# radiomatrix.net
KiCad netlist of a schematic drawn in EAGLE
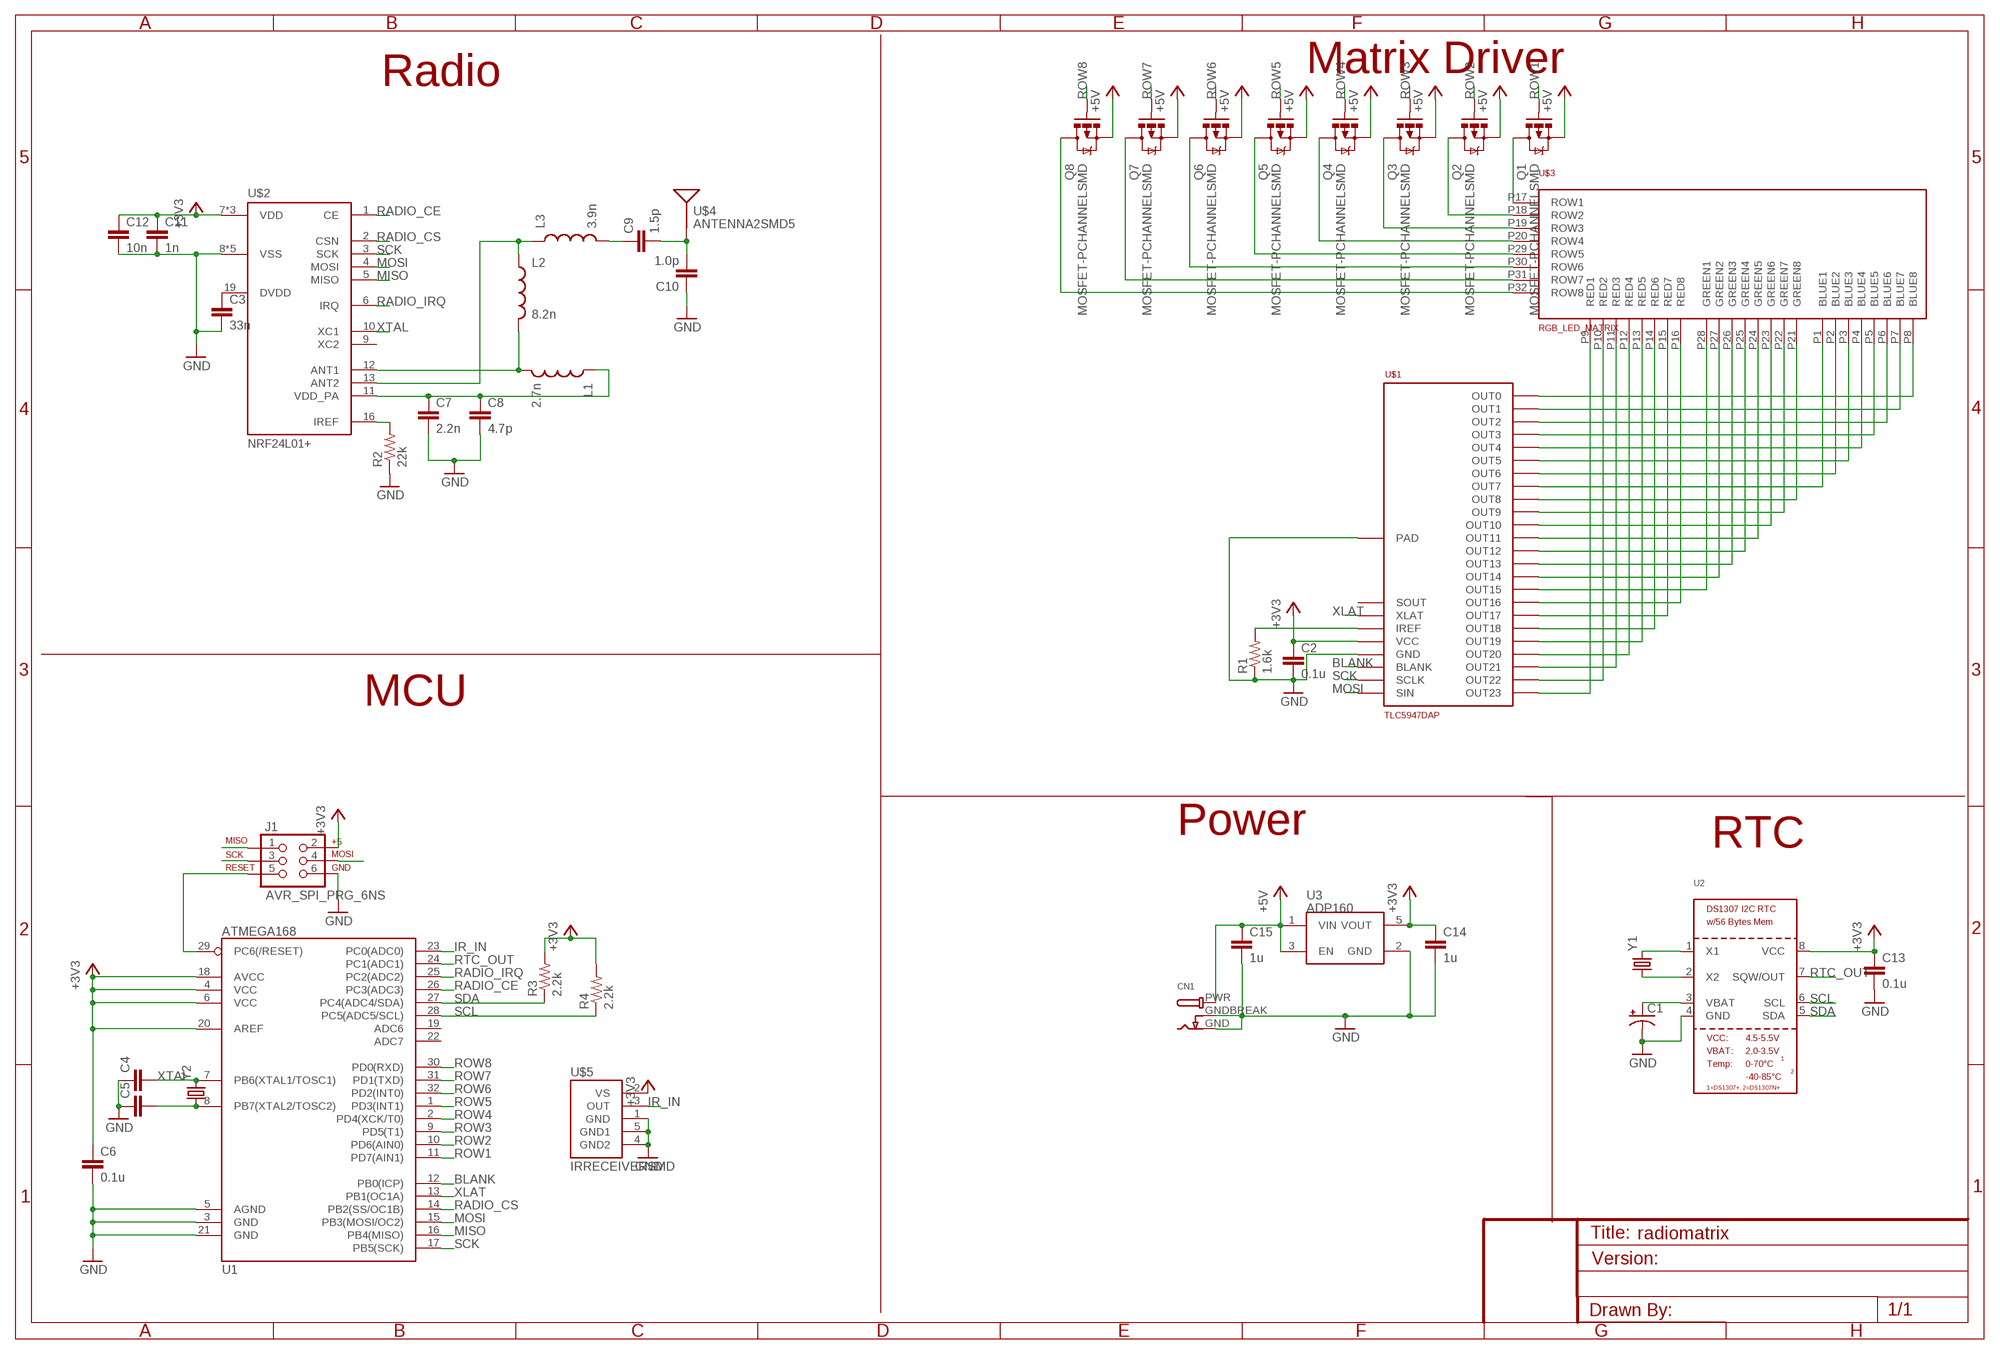
[diagram p0: schematic, sheet 1]

(export (version "E")
  (design (tool "Eeschema 10.0.6"))
  (components
    (comp (ref "C1")
      (value "SUPERCAP")
      (footprint "eagle-import:414-VA5R")
      (libsource (lib "eagle-import") (part "SUPERCAP"))
    )
    (comp (ref "C2")
      (value "0.1u")
      (footprint "eagle-import:0603-CAP")
      (libsource (lib "eagle-import") (part "CAP0603-CAP"))
    )
    (comp (ref "C3")
      (value "33n")
      (footprint "eagle-import:0603-CAP")
      (libsource (lib "eagle-import") (part "CAP0603-CAP"))
    )
    (comp (ref "C4")
      (value "CAP0603-CAP")
      (footprint "eagle-import:0603-CAP")
      (libsource (lib "eagle-import") (part "CAP0603-CAP"))
    )
    (comp (ref "C5")
      (value "CAP0603-CAP")
      (footprint "eagle-import:0603-CAP")
      (libsource (lib "eagle-import") (part "CAP0603-CAP"))
    )
    (comp (ref "C6")
      (value "0.1u")
      (footprint "eagle-import:0603-CAP")
      (libsource (lib "eagle-import") (part "CAP0603-CAP"))
    )
    (comp (ref "C7")
      (value "2.2n")
      (footprint "eagle-import:0603-CAP")
      (libsource (lib "eagle-import") (part "CAP0603-CAP"))
    )
    (comp (ref "C8")
      (value "4.7p")
      (footprint "eagle-import:0603-CAP")
      (libsource (lib "eagle-import") (part "CAP0603-CAP"))
    )
    (comp (ref "C9")
      (value "1.5p")
      (footprint "eagle-import:0603-CAP")
      (libsource (lib "eagle-import") (part "CAP0603-CAP"))
    )
    (comp (ref "C10")
      (value "1.0p")
      (footprint "eagle-import:0603-CAP")
      (libsource (lib "eagle-import") (part "CAP0603-CAP"))
    )
    (comp (ref "C11")
      (value "1n")
      (footprint "eagle-import:0603-CAP")
      (libsource (lib "eagle-import") (part "CAP0603-CAP"))
    )
    (comp (ref "C12")
      (value "10n")
      (footprint "eagle-import:0603-CAP")
      (libsource (lib "eagle-import") (part "CAP0603-CAP"))
    )
    (comp (ref "C13")
      (value "0.1u")
      (footprint "eagle-import:0603-CAP")
      (libsource (lib "eagle-import") (part "CAP0603-CAP"))
    )
    (comp (ref "C14")
      (value "1u")
      (footprint "eagle-import:0603-CAP")
      (libsource (lib "eagle-import") (part "CAP0603-CAP"))
    )
    (comp (ref "C15")
      (value "1u")
      (footprint "eagle-import:0603-CAP")
      (libsource (lib "eagle-import") (part "CAP0603-CAP"))
    )
    (comp (ref "CN1")
      (value "DCBARREL1.3MM")
      (footprint "eagle-import:DCJACK_1.3MM_PTH")
      (libsource (lib "eagle-import") (part "DCBARREL1.3MM"))
    )
    (comp (ref "J1")
      (value "AVR_SPI_PRG_6NS")
      (footprint "eagle-import:2X3-NS")
      (libsource (lib "eagle-import") (part "AVR_SPI_PRG_6NS"))
    )
    (comp (ref "L1")
      (value "2.7n")
      (footprint "eagle-import:0603")
      (libsource (lib "eagle-import") (part "INDUCTOR0603"))
    )
    (comp (ref "L2")
      (value "8.2n")
      (footprint "eagle-import:0603")
      (libsource (lib "eagle-import") (part "INDUCTOR0603"))
    )
    (comp (ref "L3")
      (value "3.9n")
      (footprint "eagle-import:0603")
      (libsource (lib "eagle-import") (part "INDUCTOR0603"))
    )
    (comp (ref "Q1")
      (value "MOSFET-PCHANNELSMD")
      (footprint "eagle-import:SOT23-3")
      (libsource (lib "eagle-import") (part "MOSFET-PCHANNELSMD"))
    )
    (comp (ref "Q2")
      (value "MOSFET-PCHANNELSMD")
      (footprint "eagle-import:SOT23-3")
      (libsource (lib "eagle-import") (part "MOSFET-PCHANNELSMD"))
    )
    (comp (ref "Q3")
      (value "MOSFET-PCHANNELSMD")
      (footprint "eagle-import:SOT23-3")
      (libsource (lib "eagle-import") (part "MOSFET-PCHANNELSMD"))
    )
    (comp (ref "Q4")
      (value "MOSFET-PCHANNELSMD")
      (footprint "eagle-import:SOT23-3")
      (libsource (lib "eagle-import") (part "MOSFET-PCHANNELSMD"))
    )
    (comp (ref "Q5")
      (value "MOSFET-PCHANNELSMD")
      (footprint "eagle-import:SOT23-3")
      (libsource (lib "eagle-import") (part "MOSFET-PCHANNELSMD"))
    )
    (comp (ref "Q6")
      (value "MOSFET-PCHANNELSMD")
      (footprint "eagle-import:SOT23-3")
      (libsource (lib "eagle-import") (part "MOSFET-PCHANNELSMD"))
    )
    (comp (ref "Q7")
      (value "MOSFET-PCHANNELSMD")
      (footprint "eagle-import:SOT23-3")
      (libsource (lib "eagle-import") (part "MOSFET-PCHANNELSMD"))
    )
    (comp (ref "Q8")
      (value "MOSFET-PCHANNELSMD")
      (footprint "eagle-import:SOT23-3")
      (libsource (lib "eagle-import") (part "MOSFET-PCHANNELSMD"))
    )
    (comp (ref "R1")
      (value "1.6k")
      (footprint "eagle-import:0603-RES")
      (libsource (lib "eagle-import") (part "RESISTOR0603-RES"))
    )
    (comp (ref "R2")
      (value "22k")
      (footprint "eagle-import:0603-RES")
      (libsource (lib "eagle-import") (part "RESISTOR0603-RES"))
    )
    (comp (ref "R3")
      (value "2.2k")
      (footprint "eagle-import:0603-RES")
      (libsource (lib "eagle-import") (part "RESISTOR0603-RES"))
    )
    (comp (ref "R4")
      (value "2.2k")
      (footprint "eagle-import:0603-RES")
      (libsource (lib "eagle-import") (part "RESISTOR0603-RES"))
    )
    (comp (ref "U$1")
      (value "TLC5947DAP")
      (footprint "eagle-import:HTSSOP32DAP")
      (libsource (lib "eagle-import") (part "TLC5947DAP"))
    )
    (comp (ref "U$2")
      (value "NRF24L01+")
      (footprint "eagle-import:QFN20")
      (libsource (lib "eagle-import") (part "NRF24L01+"))
    )
    (comp (ref "U$3")
      (value "RGB_LED_MATRIX")
      (footprint "eagle-import:RGB_LED_MATRIX_60MM")
      (libsource (lib "eagle-import") (part "RGB_LED_MATRIX"))
    )
    (comp (ref "U$4")
      (value "ANTENNA2SMD5")
      (footprint "eagle-import:ANTENNA-CHIP5")
      (libsource (lib "eagle-import") (part "ANTENNA2SMD5"))
    )
    (comp (ref "U$5")
      (value "IRRECEIVERSMD")
      (footprint "eagle-import:TSOP8523")
      (libsource (lib "eagle-import") (part "IRRECEIVERSMD"))
    )
    (comp (ref "U1")
      (value "ATMEGA168")
      (footprint "eagle-import:TQFP32-08")
      (libsource (lib "eagle-import") (part "ATMEGA168"))
    )
    (comp (ref "U2")
      (value "RTC_DS1307")
      (footprint "eagle-import:SOIC8_150MIL")
      (libsource (lib "eagle-import") (part "RTC_DS1307"))
    )
    (comp (ref "U3")
      (value "ADP160")
      (footprint "eagle-import:SOT23-5")
      (libsource (lib "eagle-import") (part "ADP160"))
    )
    (comp (ref "Y1")
      (value "CRYSTAL32-SMD")
      (footprint "eagle-import:CRYSTAL-32KHZ-SMD")
      (libsource (lib "eagle-import") (part "CRYSTAL32-SMD"))
    )
    (comp (ref "Y2")
      (value "CRYSTAL5X3")
      (footprint "eagle-import:CRYSTAL-SMD-5X3")
      (libsource (lib "eagle-import") (part "CRYSTAL5X3"))
    )
  )
  (nets
    (net (code "1") (name "+3V3") (class "Default")
      (node (ref "C11") (pin "1") (pinfunction "1_1") (pintype "passive"))
      (node (ref "C12") (pin "1") (pinfunction "1_1") (pintype "passive"))
      (node (ref "C13") (pin "1") (pinfunction "1_1") (pintype "passive"))
      (node (ref "C14") (pin "1") (pinfunction "1_1") (pintype "passive"))
      (node (ref "C2") (pin "1") (pinfunction "1_1") (pintype "passive"))
      (node (ref "C6") (pin "1") (pinfunction "1_1") (pintype "passive"))
      (node (ref "J1") (pin "2") (pinfunction "2_2") (pintype "passive"))
      (node (ref "R3") (pin "2") (pinfunction "2_2") (pintype "passive"))
      (node (ref "R4") (pin "2") (pinfunction "2_2") (pintype "passive"))
      (node (ref "U$1") (pin "32") (pinfunction "VCC_32") (pintype "bidirectional"))
      (node (ref "U$2") (pin "15") (pinfunction "VDD_15") (pintype "bidirectional"))
      (node (ref "U$2") (pin "18") (pinfunction "VDD_18") (pintype "bidirectional"))
      (node (ref "U$2") (pin "7") (pinfunction "VDD_7") (pintype "bidirectional"))
      (node (ref "U$5") (pin "2") (pinfunction "VS_2") (pintype "bidirectional"))
      (node (ref "U1") (pin "18") (pinfunction "AVCC_18") (pintype "bidirectional"))
      (node (ref "U1") (pin "20") (pinfunction "AREF_20") (pintype "bidirectional"))
      (node (ref "U1") (pin "4") (pinfunction "VCC_4") (pintype "bidirectional"))
      (node (ref "U1") (pin "6") (pinfunction "VCC_6") (pintype "bidirectional"))
      (node (ref "U2") (pin "8") (pinfunction "VCC_8") (pintype "bidirectional"))
      (node (ref "U3") (pin "5") (pinfunction "VOUT_5") (pintype "bidirectional"))
    )
    (net (code "2") (name "+5V") (class "Default")
      (node (ref "C15") (pin "1") (pinfunction "1_1") (pintype "passive"))
      (node (ref "CN1") (pin "PWR") (pinfunction "PWR_PWR") (pintype "power_in"))
      (node (ref "Q1") (pin "2") (pinfunction "S_2") (pintype "passive"))
      (node (ref "Q2") (pin "2") (pinfunction "S_2") (pintype "passive"))
      (node (ref "Q3") (pin "2") (pinfunction "S_2") (pintype "passive"))
      (node (ref "Q4") (pin "2") (pinfunction "S_2") (pintype "passive"))
      (node (ref "Q5") (pin "2") (pinfunction "S_2") (pintype "passive"))
      (node (ref "Q6") (pin "2") (pinfunction "S_2") (pintype "passive"))
      (node (ref "Q7") (pin "2") (pinfunction "S_2") (pintype "passive"))
      (node (ref "Q8") (pin "2") (pinfunction "S_2") (pintype "passive"))
      (node (ref "U3") (pin "1") (pinfunction "VIN_1") (pintype "bidirectional"))
      (node (ref "U3") (pin "3") (pinfunction "EN_3") (pintype "bidirectional"))
    )
    (net (code "3") (name "/BLANK") (class "Default")
      (node (ref "U$1") (pin "2") (pinfunction "BLANK_2") (pintype "bidirectional"))
      (node (ref "U1") (pin "12") (pinfunction "PB0(ICP)_12") (pintype "bidirectional"))
    )
    (net (code "4") (name "/IR_IN") (class "Default")
      (node (ref "U$5") (pin "3") (pinfunction "OUT_3") (pintype "bidirectional"))
      (node (ref "U1") (pin "23") (pinfunction "PC0(ADC0)_23") (pintype "bidirectional"))
    )
    (net (code "5") (name "/MISO") (class "Default")
      (node (ref "J1") (pin "1") (pinfunction "1_1") (pintype "passive"))
      (node (ref "U$2") (pin "5") (pinfunction "MISO_5") (pintype "bidirectional"))
      (node (ref "U1") (pin "16") (pinfunction "PB4(MISO)_16") (pintype "bidirectional"))
    )
    (net (code "6") (name "/MOSI") (class "Default")
      (node (ref "J1") (pin "4") (pinfunction "4_4") (pintype "passive"))
      (node (ref "U$1") (pin "4") (pinfunction "SIN_4") (pintype "bidirectional"))
      (node (ref "U$2") (pin "4") (pinfunction "MOSI_4") (pintype "bidirectional"))
      (node (ref "U1") (pin "15") (pinfunction "PB3(MOSI/OC2)_15") (pintype "bidirectional"))
    )
    (net (code "7") (name "/RADIO_CE") (class "Default")
      (node (ref "U$2") (pin "1") (pinfunction "CE_1") (pintype "bidirectional"))
      (node (ref "U1") (pin "26") (pinfunction "PC3(ADC3)_26") (pintype "bidirectional"))
    )
    (net (code "8") (name "/RADIO_CS") (class "Default")
      (node (ref "U$2") (pin "2") (pinfunction "CSN_2") (pintype "bidirectional"))
      (node (ref "U1") (pin "14") (pinfunction "PB2(SS/OC1B)_14") (pintype "bidirectional"))
    )
    (net (code "9") (name "/RADIO_IRQ") (class "Default")
      (node (ref "U$2") (pin "6") (pinfunction "IRQ_6") (pintype "bidirectional"))
      (node (ref "U1") (pin "25") (pinfunction "PC2(ADC2)_25") (pintype "bidirectional"))
    )
    (net (code "10") (name "/ROW1") (class "Default")
      (node (ref "Q1") (pin "1") (pinfunction "G_1") (pintype "passive"))
      (node (ref "U1") (pin "11") (pinfunction "PD7(AIN1)_11") (pintype "bidirectional"))
    )
    (net (code "11") (name "/ROW2") (class "Default")
      (node (ref "Q2") (pin "1") (pinfunction "G_1") (pintype "passive"))
      (node (ref "U1") (pin "10") (pinfunction "PD6(AIN0)_10") (pintype "bidirectional"))
    )
    (net (code "12") (name "/ROW3") (class "Default")
      (node (ref "Q3") (pin "1") (pinfunction "G_1") (pintype "passive"))
      (node (ref "U1") (pin "9") (pinfunction "PD5(T1)_9") (pintype "bidirectional"))
    )
    (net (code "13") (name "/ROW4") (class "Default")
      (node (ref "Q4") (pin "1") (pinfunction "G_1") (pintype "passive"))
      (node (ref "U1") (pin "2") (pinfunction "PD4(XCK/T0)_2") (pintype "bidirectional"))
    )
    (net (code "14") (name "/ROW5") (class "Default")
      (node (ref "Q5") (pin "1") (pinfunction "G_1") (pintype "passive"))
      (node (ref "U1") (pin "1") (pinfunction "PD3(INT1)_1") (pintype "bidirectional"))
    )
    (net (code "15") (name "/ROW6") (class "Default")
      (node (ref "Q6") (pin "1") (pinfunction "G_1") (pintype "passive"))
      (node (ref "U1") (pin "32") (pinfunction "PD2(INT0)_32") (pintype "bidirectional"))
    )
    (net (code "16") (name "/ROW7") (class "Default")
      (node (ref "Q7") (pin "1") (pinfunction "G_1") (pintype "passive"))
      (node (ref "U1") (pin "31") (pinfunction "PD1(TXD)_31") (pintype "bidirectional"))
    )
    (net (code "17") (name "/ROW8") (class "Default")
      (node (ref "Q8") (pin "1") (pinfunction "G_1") (pintype "passive"))
      (node (ref "U1") (pin "30") (pinfunction "PD0(RXD)_30") (pintype "bidirectional"))
    )
    (net (code "18") (name "/RTC_OUT") (class "Default")
      (node (ref "U1") (pin "24") (pinfunction "PC1(ADC1)_24") (pintype "bidirectional"))
      (node (ref "U2") (pin "7") (pinfunction "SQW/OUT_7") (pintype "bidirectional"))
    )
    (net (code "19") (name "/SCK") (class "Default")
      (node (ref "J1") (pin "3") (pinfunction "3_3") (pintype "passive"))
      (node (ref "U$1") (pin "3") (pinfunction "SCLK_3") (pintype "bidirectional"))
      (node (ref "U$2") (pin "3") (pinfunction "SCK_3") (pintype "bidirectional"))
      (node (ref "U1") (pin "17") (pinfunction "PB5(SCK)_17") (pintype "bidirectional"))
    )
    (net (code "20") (name "/SCL") (class "Default")
      (node (ref "R4") (pin "1") (pinfunction "1_1") (pintype "passive"))
      (node (ref "U1") (pin "28") (pinfunction "PC5(ADC5/SCL)_28") (pintype "bidirectional"))
      (node (ref "U2") (pin "6") (pinfunction "SCL_6") (pintype "bidirectional"))
    )
    (net (code "21") (name "/SDA") (class "Default")
      (node (ref "R3") (pin "1") (pinfunction "1_1") (pintype "passive"))
      (node (ref "U1") (pin "27") (pinfunction "PC4(ADC4/SDA)_27") (pintype "bidirectional"))
      (node (ref "U2") (pin "5") (pinfunction "SDA_5") (pintype "bidirectional"))
    )
    (net (code "22") (name "/XLAT") (class "Default")
      (node (ref "U$1") (pin "30") (pinfunction "XLAT_30") (pintype "bidirectional"))
      (node (ref "U1") (pin "13") (pinfunction "PB1(OC1A)_13") (pintype "bidirectional"))
    )
    (net (code "23") (name "/XTAL") (class "Default")
      (node (ref "C4") (pin "2") (pinfunction "2_2") (pintype "passive"))
      (node (ref "U$2") (pin "10") (pinfunction "XC1_10") (pintype "bidirectional"))
      (node (ref "U1") (pin "7") (pinfunction "PB6(XTAL1/TOSC1)_7") (pintype "bidirectional"))
      (node (ref "Y2") (pin "3") (pinfunction "2_3") (pintype "passive"))
    )
    (net (code "24") (name "GND") (class "Default")
      (node (ref "C1") (pin "-") (pinfunction "-_-") (pintype "passive"))
      (node (ref "C10") (pin "1") (pinfunction "1_1") (pintype "passive"))
      (node (ref "C11") (pin "2") (pinfunction "2_2") (pintype "passive"))
      (node (ref "C12") (pin "2") (pinfunction "2_2") (pintype "passive"))
      (node (ref "C13") (pin "2") (pinfunction "2_2") (pintype "passive"))
      (node (ref "C14") (pin "2") (pinfunction "2_2") (pintype "passive"))
      (node (ref "C15") (pin "2") (pinfunction "2_2") (pintype "passive"))
      (node (ref "C2") (pin "2") (pinfunction "2_2") (pintype "passive"))
      (node (ref "C3") (pin "2") (pinfunction "2_2") (pintype "passive"))
      (node (ref "C4") (pin "1") (pinfunction "1_1") (pintype "passive"))
      (node (ref "C5") (pin "1") (pinfunction "1_1") (pintype "passive"))
      (node (ref "C6") (pin "2") (pinfunction "2_2") (pintype "passive"))
      (node (ref "C7") (pin "2") (pinfunction "2_2") (pintype "passive"))
      (node (ref "C8") (pin "2") (pinfunction "2_2") (pintype "passive"))
      (node (ref "CN1") (pin "GND") (pinfunction "GND_GND") (pintype "power_in"))
      (node (ref "CN1") (pin "GNDBREAK") (pinfunction "GNDBREAK_GNDBREAK") (pintype "power_in"))
      (node (ref "J1") (pin "6") (pinfunction "6_6") (pintype "passive"))
      (node (ref "R1") (pin "1") (pinfunction "1_1") (pintype "passive"))
      (node (ref "R2") (pin "1") (pinfunction "1_1") (pintype "passive"))
      (node (ref "U$1") (pin "1") (pinfunction "GND_1") (pintype "bidirectional"))
      (node (ref "U$1") (pin "EXP") (pinfunction "PAD_EXP") (pintype "bidirectional"))
      (node (ref "U$2") (pin "14") (pinfunction "VSS_14") (pintype "bidirectional"))
      (node (ref "U$2") (pin "17") (pinfunction "VSS_17") (pintype "bidirectional"))
      (node (ref "U$2") (pin "20") (pinfunction "VSS_20") (pintype "bidirectional"))
      (node (ref "U$2") (pin "8") (pinfunction "VSS_8") (pintype "bidirectional"))
      (node (ref "U$2") (pin "EXP") (pinfunction "VSS_EXP") (pintype "bidirectional"))
      (node (ref "U$5") (pin "1") (pinfunction "GND_1") (pintype "bidirectional"))
      (node (ref "U$5") (pin "4") (pinfunction "GND2_4") (pintype "bidirectional"))
      (node (ref "U$5") (pin "5") (pinfunction "GND1_5") (pintype "bidirectional"))
      (node (ref "U1") (pin "21") (pinfunction "GND_21") (pintype "bidirectional"))
      (node (ref "U1") (pin "3") (pinfunction "GND_3") (pintype "bidirectional"))
      (node (ref "U1") (pin "5") (pinfunction "AGND_5") (pintype "bidirectional"))
      (node (ref "U2") (pin "4") (pinfunction "GND_4") (pintype "bidirectional"))
      (node (ref "U3") (pin "2") (pinfunction "GND_2") (pintype "bidirectional"))
    )
    (net (code "25") (name "Net-(C9-Pad1)") (class "Default")
      (node (ref "C9") (pin "1") (pinfunction "1_1") (pintype "passive"))
      (node (ref "L3") (pin "2") (pinfunction "2_2") (pintype "passive"))
    )
    (net (code "26") (name "Net-(Q1-D)") (class "Default")
      (node (ref "Q1") (pin "3") (pinfunction "D_3") (pintype "passive"))
      (node (ref "U$3") (pin "P17") (pinfunction "ROW1_P17") (pintype "power_in"))
    )
    (net (code "27") (name "Net-(Q2-D)") (class "Default")
      (node (ref "Q2") (pin "3") (pinfunction "D_3") (pintype "passive"))
      (node (ref "U$3") (pin "P18") (pinfunction "ROW2_P18") (pintype "power_in"))
    )
    (net (code "28") (name "Net-(Q3-D)") (class "Default")
      (node (ref "Q3") (pin "3") (pinfunction "D_3") (pintype "passive"))
      (node (ref "U$3") (pin "P19") (pinfunction "ROW3_P19") (pintype "power_in"))
    )
    (net (code "29") (name "Net-(Q4-D)") (class "Default")
      (node (ref "Q4") (pin "3") (pinfunction "D_3") (pintype "passive"))
      (node (ref "U$3") (pin "P20") (pinfunction "ROW4_P20") (pintype "power_in"))
    )
    (net (code "30") (name "Net-(Q5-D)") (class "Default")
      (node (ref "Q5") (pin "3") (pinfunction "D_3") (pintype "passive"))
      (node (ref "U$3") (pin "P29") (pinfunction "ROW5_P29") (pintype "power_in"))
    )
    (net (code "31") (name "Net-(Q6-D)") (class "Default")
      (node (ref "Q6") (pin "3") (pinfunction "D_3") (pintype "passive"))
      (node (ref "U$3") (pin "P30") (pinfunction "ROW6_P30") (pintype "power_in"))
    )
    (net (code "32") (name "Net-(Q7-D)") (class "Default")
      (node (ref "Q7") (pin "3") (pinfunction "D_3") (pintype "passive"))
      (node (ref "U$3") (pin "P31") (pinfunction "ROW7_P31") (pintype "power_in"))
    )
    (net (code "33") (name "Net-(Q8-D)") (class "Default")
      (node (ref "Q8") (pin "3") (pinfunction "D_3") (pintype "passive"))
      (node (ref "U$3") (pin "P32") (pinfunction "ROW8_P32") (pintype "power_in"))
    )
    (net (code "34") (name "Net-(U$1-IREF)") (class "Default")
      (node (ref "R1") (pin "2") (pinfunction "2_2") (pintype "passive"))
      (node (ref "U$1") (pin "31") (pinfunction "IREF_31") (pintype "bidirectional"))
    )
    (net (code "35") (name "Net-(U$1-OUT0)") (class "Default")
      (node (ref "U$1") (pin "5") (pinfunction "OUT0_5") (pintype "bidirectional"))
      (node (ref "U$3") (pin "P8") (pinfunction "BLUE8_P8") (pintype "power_in"))
    )
    (net (code "36") (name "Net-(U$1-OUT1)") (class "Default")
      (node (ref "U$1") (pin "6") (pinfunction "OUT1_6") (pintype "bidirectional"))
      (node (ref "U$3") (pin "P7") (pinfunction "BLUE7_P7") (pintype "power_in"))
    )
    (net (code "37") (name "Net-(U$1-OUT2)") (class "Default")
      (node (ref "U$1") (pin "7") (pinfunction "OUT2_7") (pintype "bidirectional"))
      (node (ref "U$3") (pin "P6") (pinfunction "BLUE6_P6") (pintype "power_in"))
    )
    (net (code "38") (name "Net-(U$1-OUT3)") (class "Default")
      (node (ref "U$1") (pin "8") (pinfunction "OUT3_8") (pintype "bidirectional"))
      (node (ref "U$3") (pin "P5") (pinfunction "BLUE5_P5") (pintype "power_in"))
    )
    (net (code "39") (name "Net-(U$1-OUT4)") (class "Default")
      (node (ref "U$1") (pin "9") (pinfunction "OUT4_9") (pintype "bidirectional"))
      (node (ref "U$3") (pin "P4") (pinfunction "BLUE4_P4") (pintype "power_in"))
    )
    (net (code "40") (name "Net-(U$1-OUT5)") (class "Default")
      (node (ref "U$1") (pin "10") (pinfunction "OUT5_10") (pintype "bidirectional"))
      (node (ref "U$3") (pin "P3") (pinfunction "BLUE3_P3") (pintype "power_in"))
    )
    (net (code "41") (name "Net-(U$1-OUT6)") (class "Default")
      (node (ref "U$1") (pin "11") (pinfunction "OUT6_11") (pintype "bidirectional"))
      (node (ref "U$3") (pin "P2") (pinfunction "BLUE2_P2") (pintype "power_in"))
    )
    (net (code "42") (name "Net-(U$1-OUT7)") (class "Default")
      (node (ref "U$1") (pin "12") (pinfunction "OUT7_12") (pintype "bidirectional"))
      (node (ref "U$3") (pin "P1") (pinfunction "BLUE1_P1") (pintype "power_in"))
    )
    (net (code "43") (name "Net-(U$1-OUT8)") (class "Default")
      (node (ref "U$1") (pin "13") (pinfunction "OUT8_13") (pintype "bidirectional"))
      (node (ref "U$3") (pin "P21") (pinfunction "GREEN8_P21") (pintype "power_in"))
    )
    (net (code "44") (name "Net-(U$1-OUT9)") (class "Default")
      (node (ref "U$1") (pin "14") (pinfunction "OUT9_14") (pintype "bidirectional"))
      (node (ref "U$3") (pin "P22") (pinfunction "GREEN7_P22") (pintype "power_in"))
    )
    (net (code "45") (name "Net-(U$1-OUT10)") (class "Default")
      (node (ref "U$1") (pin "15") (pinfunction "OUT10_15") (pintype "bidirectional"))
      (node (ref "U$3") (pin "P23") (pinfunction "GREEN6_P23") (pintype "power_in"))
    )
    (net (code "46") (name "Net-(U$1-OUT11)") (class "Default")
      (node (ref "U$1") (pin "16") (pinfunction "OUT11_16") (pintype "bidirectional"))
      (node (ref "U$3") (pin "P24") (pinfunction "GREEN5_P24") (pintype "power_in"))
    )
    (net (code "47") (name "Net-(U$1-OUT12)") (class "Default")
      (node (ref "U$1") (pin "17") (pinfunction "OUT12_17") (pintype "bidirectional"))
      (node (ref "U$3") (pin "P25") (pinfunction "GREEN4_P25") (pintype "power_in"))
    )
    (net (code "48") (name "Net-(U$1-OUT13)") (class "Default")
      (node (ref "U$1") (pin "18") (pinfunction "OUT13_18") (pintype "bidirectional"))
      (node (ref "U$3") (pin "P26") (pinfunction "GREEN3_P26") (pintype "power_in"))
    )
    (net (code "49") (name "Net-(U$1-OUT14)") (class "Default")
      (node (ref "U$1") (pin "19") (pinfunction "OUT14_19") (pintype "bidirectional"))
      (node (ref "U$3") (pin "P27") (pinfunction "GREEN2_P27") (pintype "power_in"))
    )
    (net (code "50") (name "Net-(U$1-OUT15)") (class "Default")
      (node (ref "U$1") (pin "20") (pinfunction "OUT15_20") (pintype "bidirectional"))
      (node (ref "U$3") (pin "P28") (pinfunction "GREEN1_P28") (pintype "power_in"))
    )
    (net (code "51") (name "Net-(U$1-OUT16)") (class "Default")
      (node (ref "U$1") (pin "21") (pinfunction "OUT16_21") (pintype "bidirectional"))
      (node (ref "U$3") (pin "P16") (pinfunction "RED8_P16") (pintype "power_in"))
    )
    (net (code "52") (name "Net-(U$1-OUT17)") (class "Default")
      (node (ref "U$1") (pin "22") (pinfunction "OUT17_22") (pintype "bidirectional"))
      (node (ref "U$3") (pin "P15") (pinfunction "RED7_P15") (pintype "power_in"))
    )
    (net (code "53") (name "Net-(U$1-OUT18)") (class "Default")
      (node (ref "U$1") (pin "23") (pinfunction "OUT18_23") (pintype "bidirectional"))
      (node (ref "U$3") (pin "P14") (pinfunction "RED6_P14") (pintype "power_in"))
    )
    (net (code "54") (name "Net-(U$1-OUT19)") (class "Default")
      (node (ref "U$1") (pin "24") (pinfunction "OUT19_24") (pintype "bidirectional"))
      (node (ref "U$3") (pin "P13") (pinfunction "RED5_P13") (pintype "power_in"))
    )
    (net (code "55") (name "Net-(U$1-OUT20)") (class "Default")
      (node (ref "U$1") (pin "25") (pinfunction "OUT20_25") (pintype "bidirectional"))
      (node (ref "U$3") (pin "P12") (pinfunction "RED4_P12") (pintype "power_in"))
    )
    (net (code "56") (name "Net-(U$1-OUT21)") (class "Default")
      (node (ref "U$1") (pin "26") (pinfunction "OUT21_26") (pintype "bidirectional"))
      (node (ref "U$3") (pin "P11") (pinfunction "RED3_P11") (pintype "power_in"))
    )
    (net (code "57") (name "Net-(U$1-OUT22)") (class "Default")
      (node (ref "U$1") (pin "27") (pinfunction "OUT22_27") (pintype "bidirectional"))
      (node (ref "U$3") (pin "P10") (pinfunction "RED2_P10") (pintype "power_in"))
    )
    (net (code "58") (name "Net-(U$1-OUT23)") (class "Default")
      (node (ref "U$1") (pin "28") (pinfunction "OUT23_28") (pintype "bidirectional"))
      (node (ref "U$3") (pin "P9") (pinfunction "RED1_P9") (pintype "power_in"))
    )
    (net (code "59") (name "Net-(U$2-ANT1)") (class "Default")
      (node (ref "L1") (pin "2") (pinfunction "2_2") (pintype "passive"))
      (node (ref "L2") (pin "2") (pinfunction "2_2") (pintype "passive"))
      (node (ref "U$2") (pin "12") (pinfunction "ANT1_12") (pintype "bidirectional"))
    )
    (net (code "60") (name "Net-(U$2-ANT2)") (class "Default")
      (node (ref "L2") (pin "1") (pinfunction "1_1") (pintype "passive"))
      (node (ref "L3") (pin "1") (pinfunction "1_1") (pintype "passive"))
      (node (ref "U$2") (pin "13") (pinfunction "ANT2_13") (pintype "bidirectional"))
    )
    (net (code "61") (name "Net-(U$2-DVDD)") (class "Default")
      (node (ref "C3") (pin "1") (pinfunction "1_1") (pintype "passive"))
      (node (ref "U$2") (pin "19") (pinfunction "DVDD_19") (pintype "bidirectional"))
    )
    (net (code "62") (name "Net-(U$2-IREF)") (class "Default")
      (node (ref "R2") (pin "2") (pinfunction "2_2") (pintype "passive"))
      (node (ref "U$2") (pin "16") (pinfunction "IREF_16") (pintype "bidirectional"))
    )
    (net (code "63") (name "Net-(U$2-VDD_PA)") (class "Default")
      (node (ref "C7") (pin "1") (pinfunction "1_1") (pintype "passive"))
      (node (ref "C8") (pin "1") (pinfunction "1_1") (pintype "passive"))
      (node (ref "L1") (pin "1") (pinfunction "1_1") (pintype "passive"))
      (node (ref "U$2") (pin "11") (pinfunction "VDD_PA_11") (pintype "bidirectional"))
    )
    (net (code "64") (name "Net-(U$4-SIGNAL)") (class "Default")
      (node (ref "C10") (pin "2") (pinfunction "2_2") (pintype "passive"))
      (node (ref "C9") (pin "2") (pinfunction "2_2") (pintype "passive"))
      (node (ref "U$4") (pin "FEED") (pinfunction "SIGNAL_FEED") (pintype "bidirectional"))
    )
    (net (code "65") (name "Net-(U1-PB7(XTAL2{slash}TOSC2))") (class "Default")
      (node (ref "C5") (pin "2") (pinfunction "2_2") (pintype "passive"))
      (node (ref "U1") (pin "8") (pinfunction "PB7(XTAL2/TOSC2)_8") (pintype "bidirectional"))
      (node (ref "Y2") (pin "1") (pinfunction "1_1") (pintype "passive"))
    )
    (net (code "66") (name "Net-(U1-PC6({slash}RESET))") (class "Default")
      (node (ref "J1") (pin "5") (pinfunction "5_5") (pintype "passive"))
      (node (ref "U1") (pin "29") (pinfunction "PC6(/RESET)_29") (pintype "bidirectional"))
    )
    (net (code "67") (name "Net-(U2-VBAT)") (class "Default")
      (node (ref "C1") (pin "+") (pinfunction "+_+") (pintype "passive"))
      (node (ref "U2") (pin "3") (pinfunction "VBAT_3") (pintype "bidirectional"))
    )
    (net (code "68") (name "Net-(U2-X1)") (class "Default")
      (node (ref "U2") (pin "1") (pinfunction "X1_1") (pintype "bidirectional"))
      (node (ref "Y1") (pin "X2") (pinfunction "2_X2") (pintype "passive"))
    )
    (net (code "69") (name "Net-(U2-X2)") (class "Default")
      (node (ref "U2") (pin "2") (pinfunction "X2_2") (pintype "bidirectional"))
      (node (ref "Y1") (pin "X1") (pinfunction "1_X1") (pintype "passive"))
    )
    (net (code "70") (name "unconnected-(U$1-SOUT-Pad29)") (class "Default")
      (node (ref "U$1") (pin "29") (pinfunction "SOUT_29") (pintype "bidirectional"))
    )
    (net (code "71") (name "unconnected-(U$2-XC2-Pad9)") (class "Default")
      (node (ref "U$2") (pin "9") (pinfunction "XC2_9") (pintype "bidirectional"))
    )
    (net (code "72") (name "unconnected-(U1-ADC6-Pad19)") (class "Default")
      (node (ref "U1") (pin "19") (pinfunction "ADC6_19") (pintype "bidirectional"))
    )
    (net (code "73") (name "unconnected-(U1-ADC7-Pad22)") (class "Default")
      (node (ref "U1") (pin "22") (pinfunction "ADC7_22") (pintype "bidirectional"))
    )
  )
)
